# quadrant_tia.net
KiCad netlist of a schematic drawn in EAGLE
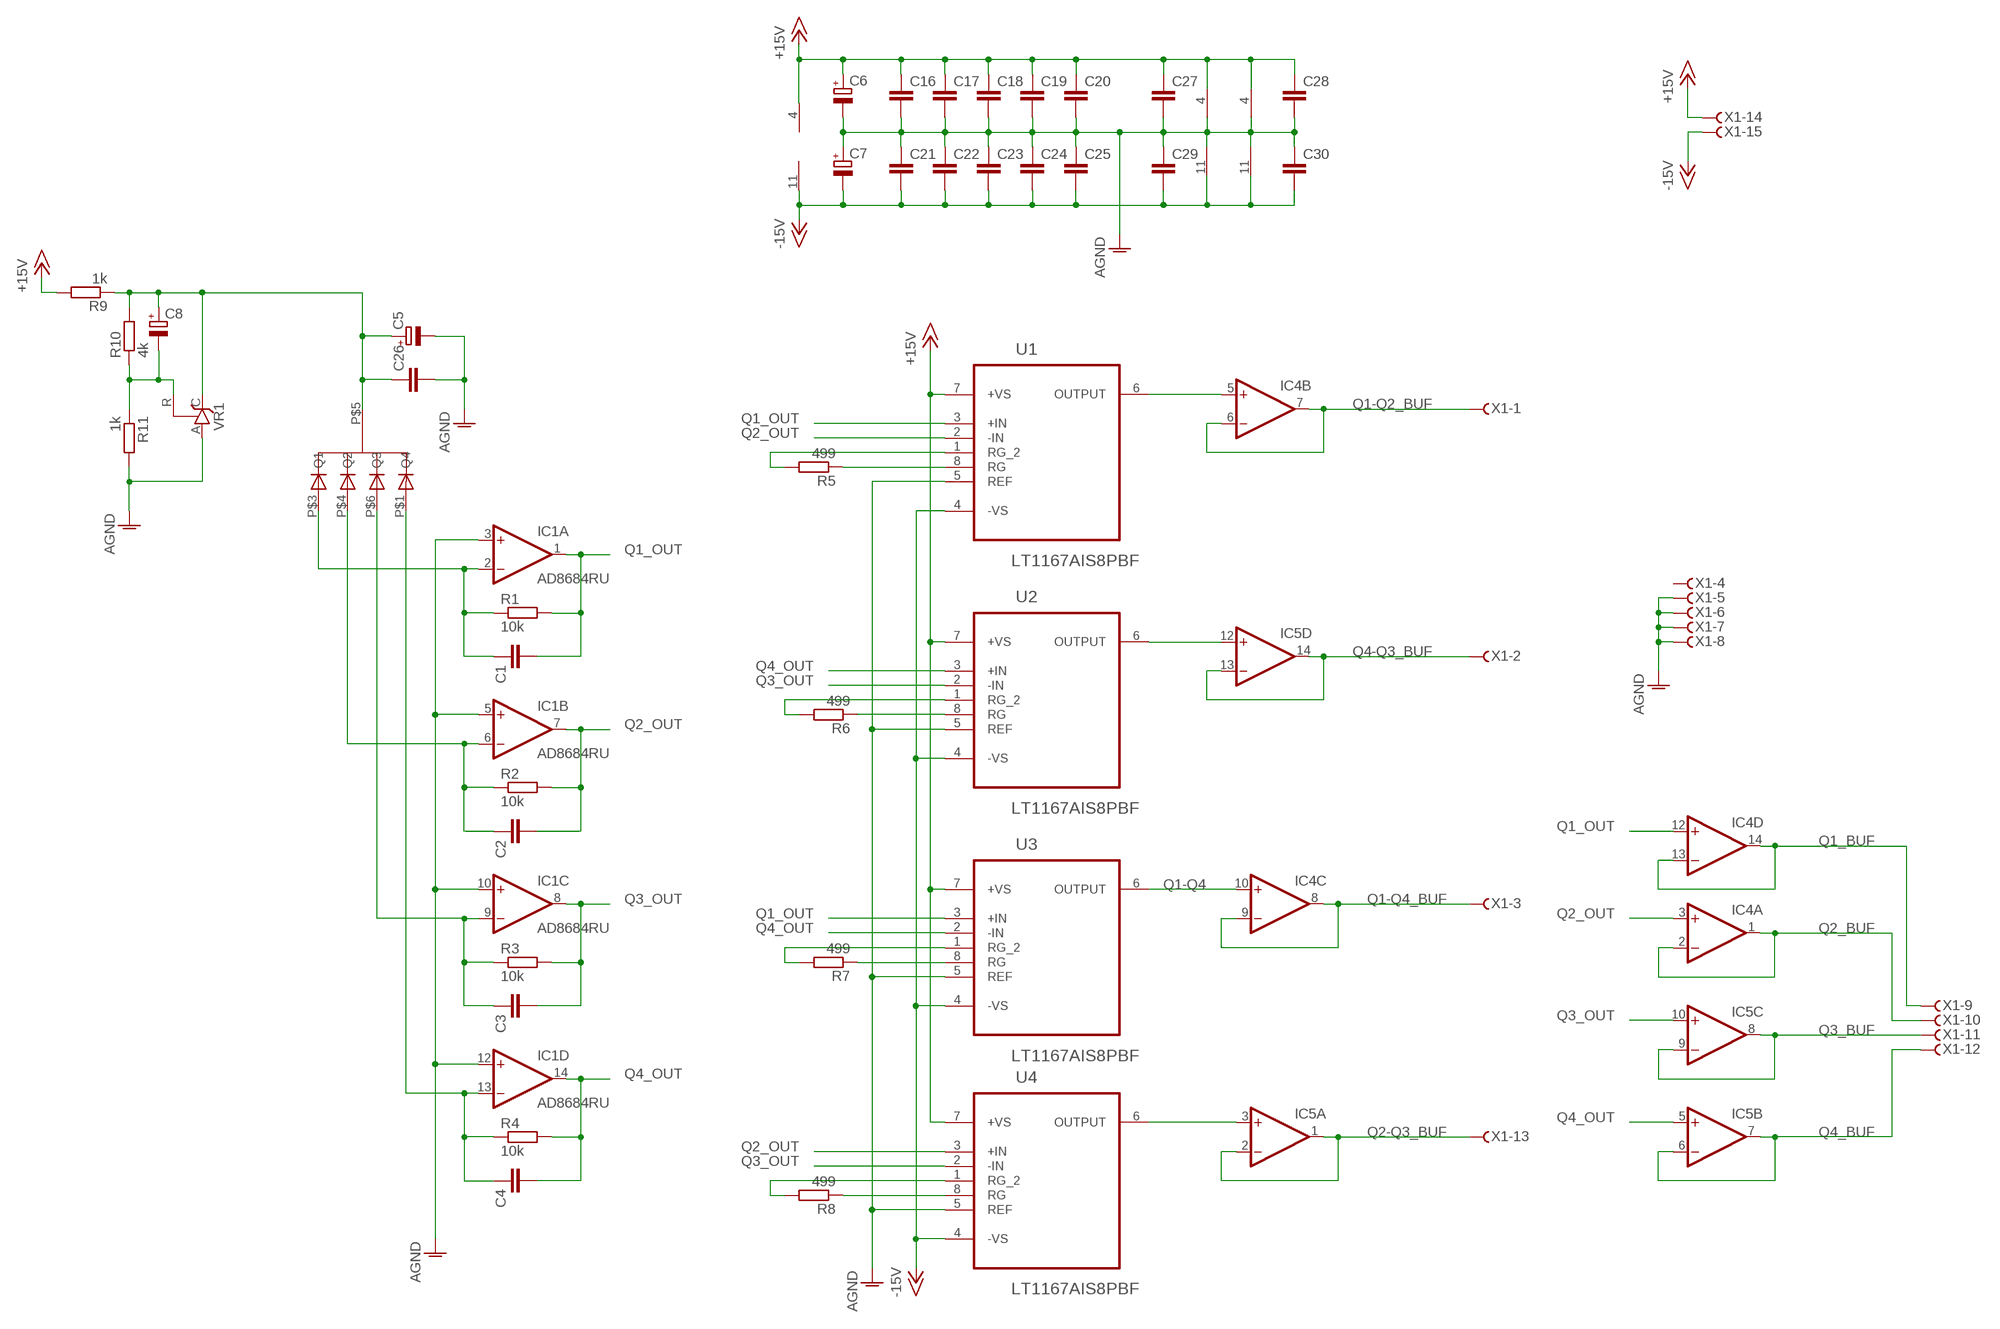
[diagram p0: schematic, sheet 1]

(export (version "E")
  (design (tool "Eeschema 10.0.6"))
  (components
    (comp (ref "C1")
      (value "C-EUC0805K")
      (footprint "eagle-import:C0805K")
      (libsource (lib "eagle-import") (part "C-EUC0805K"))
    )
    (comp (ref "C2")
      (value "C-EUC0805K")
      (footprint "eagle-import:C0805K")
      (libsource (lib "eagle-import") (part "C-EUC0805K"))
    )
    (comp (ref "C3")
      (value "C-EUC0805K")
      (footprint "eagle-import:C0805K")
      (libsource (lib "eagle-import") (part "C-EUC0805K"))
    )
    (comp (ref "C4")
      (value "C-EUC0805K")
      (footprint "eagle-import:C0805K")
      (libsource (lib "eagle-import") (part "C-EUC0805K"))
    )
    (comp (ref "C5")
      (value "CPOL-EUE5-8.5")
      (footprint "eagle-import:E5-8,5")
      (libsource (lib "eagle-import") (part "CPOL-EUE5-8.5"))
    )
    (comp (ref "C6")
      (value "CPOL-EUE5-8.5")
      (footprint "eagle-import:E5-8,5")
      (libsource (lib "eagle-import") (part "CPOL-EUE5-8.5"))
    )
    (comp (ref "C7")
      (value "CPOL-EUE5-8.5")
      (footprint "eagle-import:E5-8,5")
      (libsource (lib "eagle-import") (part "CPOL-EUE5-8.5"))
    )
    (comp (ref "C8")
      (value "CPOL-EUE5-8.5")
      (footprint "eagle-import:E5-8,5")
      (libsource (lib "eagle-import") (part "CPOL-EUE5-8.5"))
    )
    (comp (ref "C16")
      (value "C-EUC0805K")
      (footprint "eagle-import:C0805K")
      (libsource (lib "eagle-import") (part "C-EUC0805K"))
    )
    (comp (ref "C17")
      (value "C-EUC0805K")
      (footprint "eagle-import:C0805K")
      (libsource (lib "eagle-import") (part "C-EUC0805K"))
    )
    (comp (ref "C18")
      (value "C-EUC0805K")
      (footprint "eagle-import:C0805K")
      (libsource (lib "eagle-import") (part "C-EUC0805K"))
    )
    (comp (ref "C19")
      (value "C-EUC0805K")
      (footprint "eagle-import:C0805K")
      (libsource (lib "eagle-import") (part "C-EUC0805K"))
    )
    (comp (ref "C20")
      (value "C-EUC0805K")
      (footprint "eagle-import:C0805K")
      (libsource (lib "eagle-import") (part "C-EUC0805K"))
    )
    (comp (ref "C21")
      (value "C-EUC0805K")
      (footprint "eagle-import:C0805K")
      (libsource (lib "eagle-import") (part "C-EUC0805K"))
    )
    (comp (ref "C22")
      (value "C-EUC0805K")
      (footprint "eagle-import:C0805K")
      (libsource (lib "eagle-import") (part "C-EUC0805K"))
    )
    (comp (ref "C23")
      (value "C-EUC0805K")
      (footprint "eagle-import:C0805K")
      (libsource (lib "eagle-import") (part "C-EUC0805K"))
    )
    (comp (ref "C24")
      (value "C-EUC0805K")
      (footprint "eagle-import:C0805K")
      (libsource (lib "eagle-import") (part "C-EUC0805K"))
    )
    (comp (ref "C25")
      (value "C-EUC0805K")
      (footprint "eagle-import:C0805K")
      (libsource (lib "eagle-import") (part "C-EUC0805K"))
    )
    (comp (ref "C26")
      (value "C-EUC0805K")
      (footprint "eagle-import:C0805K")
      (libsource (lib "eagle-import") (part "C-EUC0805K"))
    )
    (comp (ref "C27")
      (value "C-EUC0805K")
      (footprint "eagle-import:C0805K")
      (libsource (lib "eagle-import") (part "C-EUC0805K"))
    )
    (comp (ref "C28")
      (value "C-EUC0805K")
      (footprint "eagle-import:C0805K")
      (libsource (lib "eagle-import") (part "C-EUC0805K"))
    )
    (comp (ref "C29")
      (value "C-EUC0805K")
      (footprint "eagle-import:C0805K")
      (libsource (lib "eagle-import") (part "C-EUC0805K"))
    )
    (comp (ref "C30")
      (value "C-EUC0805K")
      (footprint "eagle-import:C0805K")
      (libsource (lib "eagle-import") (part "C-EUC0805K"))
    )
    (comp (ref "IC1")
      (value "AD8684RU")
      (footprint "eagle-import:TSSOP14")
      (libsource (lib "eagle-import") (part "AD8684RU"))
    )
    (comp (ref "IC4")
      (value "4AMP_P4+11D")
      (footprint "eagle-import:SO14")
      (libsource (lib "eagle-import") (part "4AMP_P4+11D"))
    )
    (comp (ref "IC5")
      (value "4AMP_P4+11D")
      (footprint "eagle-import:SO14")
      (libsource (lib "eagle-import") (part "4AMP_P4+11D"))
    )
    (comp (ref "R1")
      (value "10k")
      (footprint "eagle-import:M1206")
      (libsource (lib "eagle-import") (part "R-EU_M1206"))
    )
    (comp (ref "R2")
      (value "10k")
      (footprint "eagle-import:M1206")
      (libsource (lib "eagle-import") (part "R-EU_M1206"))
    )
    (comp (ref "R3")
      (value "10k")
      (footprint "eagle-import:M1206")
      (libsource (lib "eagle-import") (part "R-EU_M1206"))
    )
    (comp (ref "R4")
      (value "10k")
      (footprint "eagle-import:M1206")
      (libsource (lib "eagle-import") (part "R-EU_M1206"))
    )
    (comp (ref "R5")
      (value "499")
      (footprint "eagle-import:M1206")
      (libsource (lib "eagle-import") (part "R-EU_M1206"))
    )
    (comp (ref "R6")
      (value "499")
      (footprint "eagle-import:M1206")
      (libsource (lib "eagle-import") (part "R-EU_M1206"))
    )
    (comp (ref "R7")
      (value "499")
      (footprint "eagle-import:M1206")
      (libsource (lib "eagle-import") (part "R-EU_M1206"))
    )
    (comp (ref "R8")
      (value "499")
      (footprint "eagle-import:M1206")
      (libsource (lib "eagle-import") (part "R-EU_M1206"))
    )
    (comp (ref "R9")
      (value "1k")
      (footprint "eagle-import:R0805")
      (libsource (lib "eagle-import") (part "R-EU_R0805"))
    )
    (comp (ref "R10")
      (value "4k")
      (footprint "eagle-import:R0805")
      (libsource (lib "eagle-import") (part "R-EU_R0805"))
    )
    (comp (ref "R11")
      (value "1k")
      (footprint "eagle-import:R0805")
      (libsource (lib "eagle-import") (part "R-EU_R0805"))
    )
    (comp (ref "U$1")
      (value "QP50-6")
      (footprint "eagle-import:TO-HUGE")
      (libsource (lib "eagle-import") (part "QP50-6"))
    )
    (comp (ref "U1")
      (value "LT1167AIS8PBF")
      (footprint "eagle-import:SOIC127P600X175-8N")
      (fields (field (name "MPN") "LT1167AIS8#PBF"))
      (libsource (lib "eagle-import") (part "LT1167AIS8PBF"))
    )
    (comp (ref "U2")
      (value "LT1167AIS8PBF")
      (footprint "eagle-import:SOIC127P600X175-8N")
      (fields (field (name "MPN") "LT1167AIS8#PBF"))
      (libsource (lib "eagle-import") (part "LT1167AIS8PBF"))
    )
    (comp (ref "U3")
      (value "LT1167AIS8PBF")
      (footprint "eagle-import:SOIC127P600X175-8N")
      (fields (field (name "MPN") "LT1167AIS8#PBF"))
      (libsource (lib "eagle-import") (part "LT1167AIS8PBF"))
    )
    (comp (ref "U4")
      (value "LT1167AIS8PBF")
      (footprint "eagle-import:SOIC127P600X175-8N")
      (fields (field (name "MPN") "LT1167AIS8#PBF"))
      (libsource (lib "eagle-import") (part "LT1167AIS8PBF"))
    )
    (comp (ref "VR1")
      (value "TL431CLP")
      (footprint "eagle-import:TO92-CLP")
      (libsource (lib "eagle-import") (part "TL431CLP"))
    )
    (comp (ref "X1")
      (value "F15HDHS")
      (footprint "eagle-import:HDF15H")
      (libsource (lib "eagle-import") (part "F15?SHDH"))
    )
  )
  (nets
    (net (code "1") (name "+15V") (class "Default")
      (node (ref "C16") (pin "1") (pinfunction "1_1") (pintype "passive"))
      (node (ref "C17") (pin "1") (pinfunction "1_1") (pintype "passive"))
      (node (ref "C18") (pin "1") (pinfunction "1_1") (pintype "passive"))
      (node (ref "C19") (pin "1") (pinfunction "1_1") (pintype "passive"))
      (node (ref "C20") (pin "1") (pinfunction "1_1") (pintype "passive"))
      (node (ref "C27") (pin "1") (pinfunction "1_1") (pintype "passive"))
      (node (ref "C28") (pin "1") (pinfunction "1_1") (pintype "passive"))
      (node (ref "C6") (pin "+") (pinfunction "+_+") (pintype "passive"))
      (node (ref "IC1") (pin "4") (pinfunction "V+_4") (pintype "power_in"))
      (node (ref "IC4") (pin "4") (pinfunction "V+_4") (pintype "power_in"))
      (node (ref "IC5") (pin "4") (pinfunction "V+_4") (pintype "power_in"))
      (node (ref "R9") (pin "2") (pinfunction "2_2") (pintype "passive"))
      (node (ref "U1") (pin "7") (pinfunction "+VS_7") (pintype "power_in"))
      (node (ref "U2") (pin "7") (pinfunction "+VS_7") (pintype "power_in"))
      (node (ref "U3") (pin "7") (pinfunction "+VS_7") (pintype "power_in"))
      (node (ref "U4") (pin "7") (pinfunction "+VS_7") (pintype "power_in"))
      (node (ref "X1") (pin "14") (pinfunction "F_14") (pintype "passive"))
    )
    (net (code "2") (name "-15V") (class "Default")
      (node (ref "C21") (pin "2") (pinfunction "2_2") (pintype "passive"))
      (node (ref "C22") (pin "2") (pinfunction "2_2") (pintype "passive"))
      (node (ref "C23") (pin "2") (pinfunction "2_2") (pintype "passive"))
      (node (ref "C24") (pin "2") (pinfunction "2_2") (pintype "passive"))
      (node (ref "C25") (pin "2") (pinfunction "2_2") (pintype "passive"))
      (node (ref "C29") (pin "2") (pinfunction "2_2") (pintype "passive"))
      (node (ref "C30") (pin "2") (pinfunction "2_2") (pintype "passive"))
      (node (ref "C7") (pin "-") (pinfunction "-_-") (pintype "passive"))
      (node (ref "IC1") (pin "11") (pinfunction "V-_11") (pintype "power_in"))
      (node (ref "IC4") (pin "11") (pinfunction "V-_11") (pintype "power_in"))
      (node (ref "IC5") (pin "11") (pinfunction "V-_11") (pintype "power_in"))
      (node (ref "U1") (pin "4") (pinfunction "-VS_4") (pintype "power_in"))
      (node (ref "U2") (pin "4") (pinfunction "-VS_4") (pintype "power_in"))
      (node (ref "U3") (pin "4") (pinfunction "-VS_4") (pintype "power_in"))
      (node (ref "U4") (pin "4") (pinfunction "-VS_4") (pintype "power_in"))
      (node (ref "X1") (pin "15") (pinfunction "F_15") (pintype "passive"))
    )
    (net (code "3") (name "/Q1-Q2_BUF") (class "Default")
      (node (ref "IC4") (pin "6") (pinfunction "-IN_6") (pintype "input"))
      (node (ref "IC4") (pin "7") (pinfunction "OUT_7") (pintype "output"))
      (node (ref "X1") (pin "1") (pinfunction "F_1") (pintype "passive"))
    )
    (net (code "4") (name "/Q1-Q4") (class "Default")
      (node (ref "IC4") (pin "10") (pinfunction "+IN_10") (pintype "input"))
      (node (ref "U3") (pin "6") (pinfunction "OUTPUT_6") (pintype "output"))
    )
    (net (code "5") (name "/Q1-Q4_BUF") (class "Default")
      (node (ref "IC4") (pin "8") (pinfunction "OUT_8") (pintype "output"))
      (node (ref "IC4") (pin "9") (pinfunction "-IN_9") (pintype "input"))
      (node (ref "X1") (pin "3") (pinfunction "F_3") (pintype "passive"))
    )
    (net (code "6") (name "/Q1_BUF") (class "Default")
      (node (ref "IC4") (pin "13") (pinfunction "-IN_13") (pintype "input"))
      (node (ref "IC4") (pin "14") (pinfunction "OUT_14") (pintype "output"))
      (node (ref "X1") (pin "9") (pinfunction "F_9") (pintype "passive"))
    )
    (net (code "7") (name "/Q1_OUT") (class "Default")
      (node (ref "C1") (pin "2") (pinfunction "2_2") (pintype "passive"))
      (node (ref "IC1") (pin "1") (pinfunction "OUT_1") (pintype "output"))
      (node (ref "IC4") (pin "12") (pinfunction "+IN_12") (pintype "input"))
      (node (ref "R1") (pin "2") (pinfunction "2_2") (pintype "passive"))
      (node (ref "U1") (pin "3") (pinfunction "+IN_3") (pintype "input"))
      (node (ref "U3") (pin "3") (pinfunction "+IN_3") (pintype "input"))
    )
    (net (code "8") (name "/Q2-Q3_BUF") (class "Default")
      (node (ref "IC5") (pin "1") (pinfunction "OUT_1") (pintype "output"))
      (node (ref "IC5") (pin "2") (pinfunction "-IN_2") (pintype "input"))
      (node (ref "X1") (pin "13") (pinfunction "F_13") (pintype "passive"))
    )
    (net (code "9") (name "/Q2_BUF") (class "Default")
      (node (ref "IC4") (pin "1") (pinfunction "OUT_1") (pintype "output"))
      (node (ref "IC4") (pin "2") (pinfunction "-IN_2") (pintype "input"))
      (node (ref "X1") (pin "10") (pinfunction "F_10") (pintype "passive"))
    )
    (net (code "10") (name "/Q2_OUT") (class "Default")
      (node (ref "C2") (pin "2") (pinfunction "2_2") (pintype "passive"))
      (node (ref "IC1") (pin "7") (pinfunction "OUT_7") (pintype "output"))
      (node (ref "IC4") (pin "3") (pinfunction "+IN_3") (pintype "input"))
      (node (ref "R2") (pin "2") (pinfunction "2_2") (pintype "passive"))
      (node (ref "U1") (pin "2") (pinfunction "-IN_2") (pintype "input"))
      (node (ref "U4") (pin "3") (pinfunction "+IN_3") (pintype "input"))
    )
    (net (code "11") (name "/Q3_BUF") (class "Default")
      (node (ref "IC5") (pin "8") (pinfunction "OUT_8") (pintype "output"))
      (node (ref "IC5") (pin "9") (pinfunction "-IN_9") (pintype "input"))
      (node (ref "X1") (pin "11") (pinfunction "F_11") (pintype "passive"))
    )
    (net (code "12") (name "/Q3_OUT") (class "Default")
      (node (ref "C3") (pin "2") (pinfunction "2_2") (pintype "passive"))
      (node (ref "IC1") (pin "8") (pinfunction "OUT_8") (pintype "output"))
      (node (ref "IC5") (pin "10") (pinfunction "+IN_10") (pintype "input"))
      (node (ref "R3") (pin "2") (pinfunction "2_2") (pintype "passive"))
      (node (ref "U2") (pin "2") (pinfunction "-IN_2") (pintype "input"))
      (node (ref "U4") (pin "2") (pinfunction "-IN_2") (pintype "input"))
    )
    (net (code "13") (name "/Q4-Q3_BUF") (class "Default")
      (node (ref "IC5") (pin "13") (pinfunction "-IN_13") (pintype "input"))
      (node (ref "IC5") (pin "14") (pinfunction "OUT_14") (pintype "output"))
      (node (ref "X1") (pin "2") (pinfunction "F_2") (pintype "passive"))
    )
    (net (code "14") (name "/Q4_BUF") (class "Default")
      (node (ref "IC5") (pin "6") (pinfunction "-IN_6") (pintype "input"))
      (node (ref "IC5") (pin "7") (pinfunction "OUT_7") (pintype "output"))
      (node (ref "X1") (pin "12") (pinfunction "F_12") (pintype "passive"))
    )
    (net (code "15") (name "/Q4_OUT") (class "Default")
      (node (ref "C4") (pin "2") (pinfunction "2_2") (pintype "passive"))
      (node (ref "IC1") (pin "14") (pinfunction "OUT_14") (pintype "output"))
      (node (ref "IC5") (pin "5") (pinfunction "+IN_5") (pintype "input"))
      (node (ref "R4") (pin "2") (pinfunction "2_2") (pintype "passive"))
      (node (ref "U2") (pin "3") (pinfunction "+IN_3") (pintype "input"))
      (node (ref "U3") (pin "2") (pinfunction "-IN_2") (pintype "input"))
    )
    (net (code "16") (name "AGND") (class "Default")
      (node (ref "C16") (pin "2") (pinfunction "2_2") (pintype "passive"))
      (node (ref "C17") (pin "2") (pinfunction "2_2") (pintype "passive"))
      (node (ref "C18") (pin "2") (pinfunction "2_2") (pintype "passive"))
      (node (ref "C19") (pin "2") (pinfunction "2_2") (pintype "passive"))
      (node (ref "C20") (pin "2") (pinfunction "2_2") (pintype "passive"))
      (node (ref "C21") (pin "1") (pinfunction "1_1") (pintype "passive"))
      (node (ref "C22") (pin "1") (pinfunction "1_1") (pintype "passive"))
      (node (ref "C23") (pin "1") (pinfunction "1_1") (pintype "passive"))
      (node (ref "C24") (pin "1") (pinfunction "1_1") (pintype "passive"))
      (node (ref "C25") (pin "1") (pinfunction "1_1") (pintype "passive"))
      (node (ref "C26") (pin "2") (pinfunction "2_2") (pintype "passive"))
      (node (ref "C27") (pin "2") (pinfunction "2_2") (pintype "passive"))
      (node (ref "C28") (pin "2") (pinfunction "2_2") (pintype "passive"))
      (node (ref "C29") (pin "1") (pinfunction "1_1") (pintype "passive"))
      (node (ref "C30") (pin "1") (pinfunction "1_1") (pintype "passive"))
      (node (ref "C5") (pin "-") (pinfunction "-_-") (pintype "passive"))
      (node (ref "C6") (pin "-") (pinfunction "-_-") (pintype "passive"))
      (node (ref "C7") (pin "+") (pinfunction "+_+") (pintype "passive"))
      (node (ref "IC1") (pin "10") (pinfunction "+IN_10") (pintype "input"))
      (node (ref "IC1") (pin "12") (pinfunction "+IN_12") (pintype "input"))
      (node (ref "IC1") (pin "3") (pinfunction "+IN_3") (pintype "input"))
      (node (ref "IC1") (pin "5") (pinfunction "+IN_5") (pintype "input"))
      (node (ref "R11") (pin "2") (pinfunction "2_2") (pintype "passive"))
      (node (ref "U1") (pin "5") (pinfunction "REF_5") (pintype "input"))
      (node (ref "U2") (pin "5") (pinfunction "REF_5") (pintype "input"))
      (node (ref "U3") (pin "5") (pinfunction "REF_5") (pintype "input"))
      (node (ref "U4") (pin "5") (pinfunction "REF_5") (pintype "input"))
      (node (ref "VR1") (pin "A") (pinfunction "A_A") (pintype "passive"))
      (node (ref "X1") (pin "5") (pinfunction "F_5") (pintype "passive"))
      (node (ref "X1") (pin "6") (pinfunction "F_6") (pintype "passive"))
      (node (ref "X1") (pin "7") (pinfunction "F_7") (pintype "passive"))
      (node (ref "X1") (pin "8") (pinfunction "F_8") (pintype "passive"))
    )
    (net (code "17") (name "Net-(C8-Pad-)") (class "Default")
      (node (ref "C8") (pin "-") (pinfunction "-_-") (pintype "passive"))
      (node (ref "R10") (pin "1") (pinfunction "1_1") (pintype "passive"))
      (node (ref "R11") (pin "1") (pinfunction "1_1") (pintype "passive"))
      (node (ref "VR1") (pin "R") (pinfunction "R_R") (pintype "passive"))
    )
    (net (code "18") (name "Net-(IC1A--IN)") (class "Default")
      (node (ref "C1") (pin "1") (pinfunction "1_1") (pintype "passive"))
      (node (ref "IC1") (pin "2") (pinfunction "-IN_2") (pintype "input"))
      (node (ref "R1") (pin "1") (pinfunction "1_1") (pintype "passive"))
      (node (ref "U$1") (pin "P$3") (pinfunction "Q1_P$3") (pintype "bidirectional"))
    )
    (net (code "19") (name "Net-(IC1B--IN)") (class "Default")
      (node (ref "C2") (pin "1") (pinfunction "1_1") (pintype "passive"))
      (node (ref "IC1") (pin "6") (pinfunction "-IN_6") (pintype "input"))
      (node (ref "R2") (pin "1") (pinfunction "1_1") (pintype "passive"))
      (node (ref "U$1") (pin "P$4") (pinfunction "Q2_P$4") (pintype "bidirectional"))
    )
    (net (code "20") (name "Net-(IC1C--IN)") (class "Default")
      (node (ref "C3") (pin "1") (pinfunction "1_1") (pintype "passive"))
      (node (ref "IC1") (pin "9") (pinfunction "-IN_9") (pintype "input"))
      (node (ref "R3") (pin "1") (pinfunction "1_1") (pintype "passive"))
      (node (ref "U$1") (pin "P$6") (pinfunction "Q3_P$6") (pintype "bidirectional"))
    )
    (net (code "21") (name "Net-(IC1D--IN)") (class "Default")
      (node (ref "C4") (pin "1") (pinfunction "1_1") (pintype "passive"))
      (node (ref "IC1") (pin "13") (pinfunction "-IN_13") (pintype "input"))
      (node (ref "R4") (pin "1") (pinfunction "1_1") (pintype "passive"))
      (node (ref "U$1") (pin "P$1") (pinfunction "Q4_P$1") (pintype "bidirectional"))
    )
    (net (code "22") (name "Net-(IC4B-+IN)") (class "Default")
      (node (ref "IC4") (pin "5") (pinfunction "+IN_5") (pintype "input"))
      (node (ref "U1") (pin "6") (pinfunction "OUTPUT_6") (pintype "output"))
    )
    (net (code "23") (name "Net-(IC5A-+IN)") (class "Default")
      (node (ref "IC5") (pin "3") (pinfunction "+IN_3") (pintype "input"))
      (node (ref "U4") (pin "6") (pinfunction "OUTPUT_6") (pintype "output"))
    )
    (net (code "24") (name "Net-(IC5D-+IN)") (class "Default")
      (node (ref "IC5") (pin "12") (pinfunction "+IN_12") (pintype "input"))
      (node (ref "U2") (pin "6") (pinfunction "OUTPUT_6") (pintype "output"))
    )
    (net (code "25") (name "Net-(U$1-C)") (class "Default")
      (node (ref "C26") (pin "1") (pinfunction "1_1") (pintype "passive"))
      (node (ref "C5") (pin "+") (pinfunction "+_+") (pintype "passive"))
      (node (ref "C8") (pin "+") (pinfunction "+_+") (pintype "passive"))
      (node (ref "R10") (pin "2") (pinfunction "2_2") (pintype "passive"))
      (node (ref "R9") (pin "1") (pinfunction "1_1") (pintype "passive"))
      (node (ref "U$1") (pin "P$5") (pinfunction "C_P$5") (pintype "bidirectional"))
      (node (ref "VR1") (pin "C") (pinfunction "C_C") (pintype "passive"))
    )
    (net (code "26") (name "Net-(U1-RG)") (class "Default")
      (node (ref "R5") (pin "1") (pinfunction "1_1") (pintype "passive"))
      (node (ref "U1") (pin "8") (pinfunction "RG_8") (pintype "passive"))
    )
    (net (code "27") (name "Net-(U1-RG_2)") (class "Default")
      (node (ref "R5") (pin "2") (pinfunction "2_2") (pintype "passive"))
      (node (ref "U1") (pin "1") (pinfunction "RG_2_1") (pintype "passive"))
    )
    (net (code "28") (name "Net-(U2-RG)") (class "Default")
      (node (ref "R6") (pin "1") (pinfunction "1_1") (pintype "passive"))
      (node (ref "U2") (pin "8") (pinfunction "RG_8") (pintype "passive"))
    )
    (net (code "29") (name "Net-(U2-RG_2)") (class "Default")
      (node (ref "R6") (pin "2") (pinfunction "2_2") (pintype "passive"))
      (node (ref "U2") (pin "1") (pinfunction "RG_2_1") (pintype "passive"))
    )
    (net (code "30") (name "Net-(U3-RG)") (class "Default")
      (node (ref "R7") (pin "1") (pinfunction "1_1") (pintype "passive"))
      (node (ref "U3") (pin "8") (pinfunction "RG_8") (pintype "passive"))
    )
    (net (code "31") (name "Net-(U3-RG_2)") (class "Default")
      (node (ref "R7") (pin "2") (pinfunction "2_2") (pintype "passive"))
      (node (ref "U3") (pin "1") (pinfunction "RG_2_1") (pintype "passive"))
    )
    (net (code "32") (name "Net-(U4-RG)") (class "Default")
      (node (ref "R8") (pin "1") (pinfunction "1_1") (pintype "passive"))
      (node (ref "U4") (pin "8") (pinfunction "RG_8") (pintype "passive"))
    )
    (net (code "33") (name "Net-(U4-RG_2)") (class "Default")
      (node (ref "R8") (pin "2") (pinfunction "2_2") (pintype "passive"))
      (node (ref "U4") (pin "1") (pinfunction "RG_2_1") (pintype "passive"))
    )
    (net (code "34") (name "unconnected-(X1J-F-Pad4)") (class "Default")
      (node (ref "X1") (pin "4") (pinfunction "F_4") (pintype "passive"))
    )
  )
)
